# AV_Board.net
KiCad netlist of a schematic drawn in EAGLE
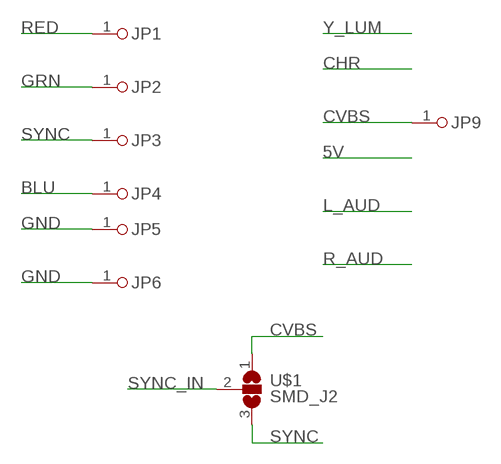
[diagram p0: schematic, sheet 1]

(export (version "E")
  (design (tool "Eeschema 10.0.6"))
  (components
    (comp (ref "JP1")
      (value "PINHD-1X1")
      (footprint "eagle-import:1X01")
      (libsource (lib "eagle-import") (part "PINHD-1X1"))
    )
    (comp (ref "JP2")
      (value "PINHD-1X1")
      (footprint "eagle-import:1X01")
      (libsource (lib "eagle-import") (part "PINHD-1X1"))
    )
    (comp (ref "JP3")
      (value "PINHD-1X1")
      (footprint "eagle-import:1X01")
      (libsource (lib "eagle-import") (part "PINHD-1X1"))
    )
    (comp (ref "JP4")
      (value "PINHD-1X1")
      (footprint "eagle-import:1X01")
      (libsource (lib "eagle-import") (part "PINHD-1X1"))
    )
    (comp (ref "JP5")
      (value "PINHD-1X1")
      (footprint "eagle-import:1X01")
      (libsource (lib "eagle-import") (part "PINHD-1X1"))
    )
    (comp (ref "JP6")
      (value "PINHD-1X1")
      (footprint "eagle-import:1X01")
      (libsource (lib "eagle-import") (part "PINHD-1X1"))
    )
    (comp (ref "JP9")
      (value "PINHD-1X1")
      (footprint "eagle-import:1X01")
      (libsource (lib "eagle-import") (part "PINHD-1X1"))
    )
    (comp (ref "U$1")
      (value "SMD_J2")
      (footprint "eagle-import:SJ_2")
      (libsource (lib "eagle-import") (part "SMD_J2"))
    )
  )
  (nets
    (net (code "2") (name "/BLU") (class "Default")
      (node (ref "JP4") (pin "1") (pinfunction "1_1") (pintype "passive"))
    )
    (net (code "4") (name "/CVBS") (class "Default")
      (node (ref "JP9") (pin "1") (pinfunction "1_1") (pintype "passive"))
      (node (ref "U$1") (pin "1") (pinfunction "1_1") (pintype "passive"))
    )
    (net (code "5") (name "/GND") (class "Default")
      (node (ref "JP5") (pin "1") (pinfunction "1_1") (pintype "passive"))
      (node (ref "JP6") (pin "1") (pinfunction "1_1") (pintype "passive"))
    )
    (net (code "6") (name "/GRN") (class "Default")
      (node (ref "JP2") (pin "1") (pinfunction "1_1") (pintype "passive"))
    )
    (net (code "8") (name "/RED") (class "Default")
      (node (ref "JP1") (pin "1") (pinfunction "1_1") (pintype "passive"))
    )
    (net (code "10") (name "/SYNC") (class "Default")
      (node (ref "JP3") (pin "1") (pinfunction "1_1") (pintype "passive"))
      (node (ref "U$1") (pin "3") (pinfunction "3_3") (pintype "passive"))
    )
    (net (code "11") (name "/SYNC_IN") (class "Default")
      (node (ref "U$1") (pin "2") (pinfunction "2_2") (pintype "passive"))
    )
  )
)
